# DDR3LChip.net
KiCad netlist of a schematic drawn in Altium Designer
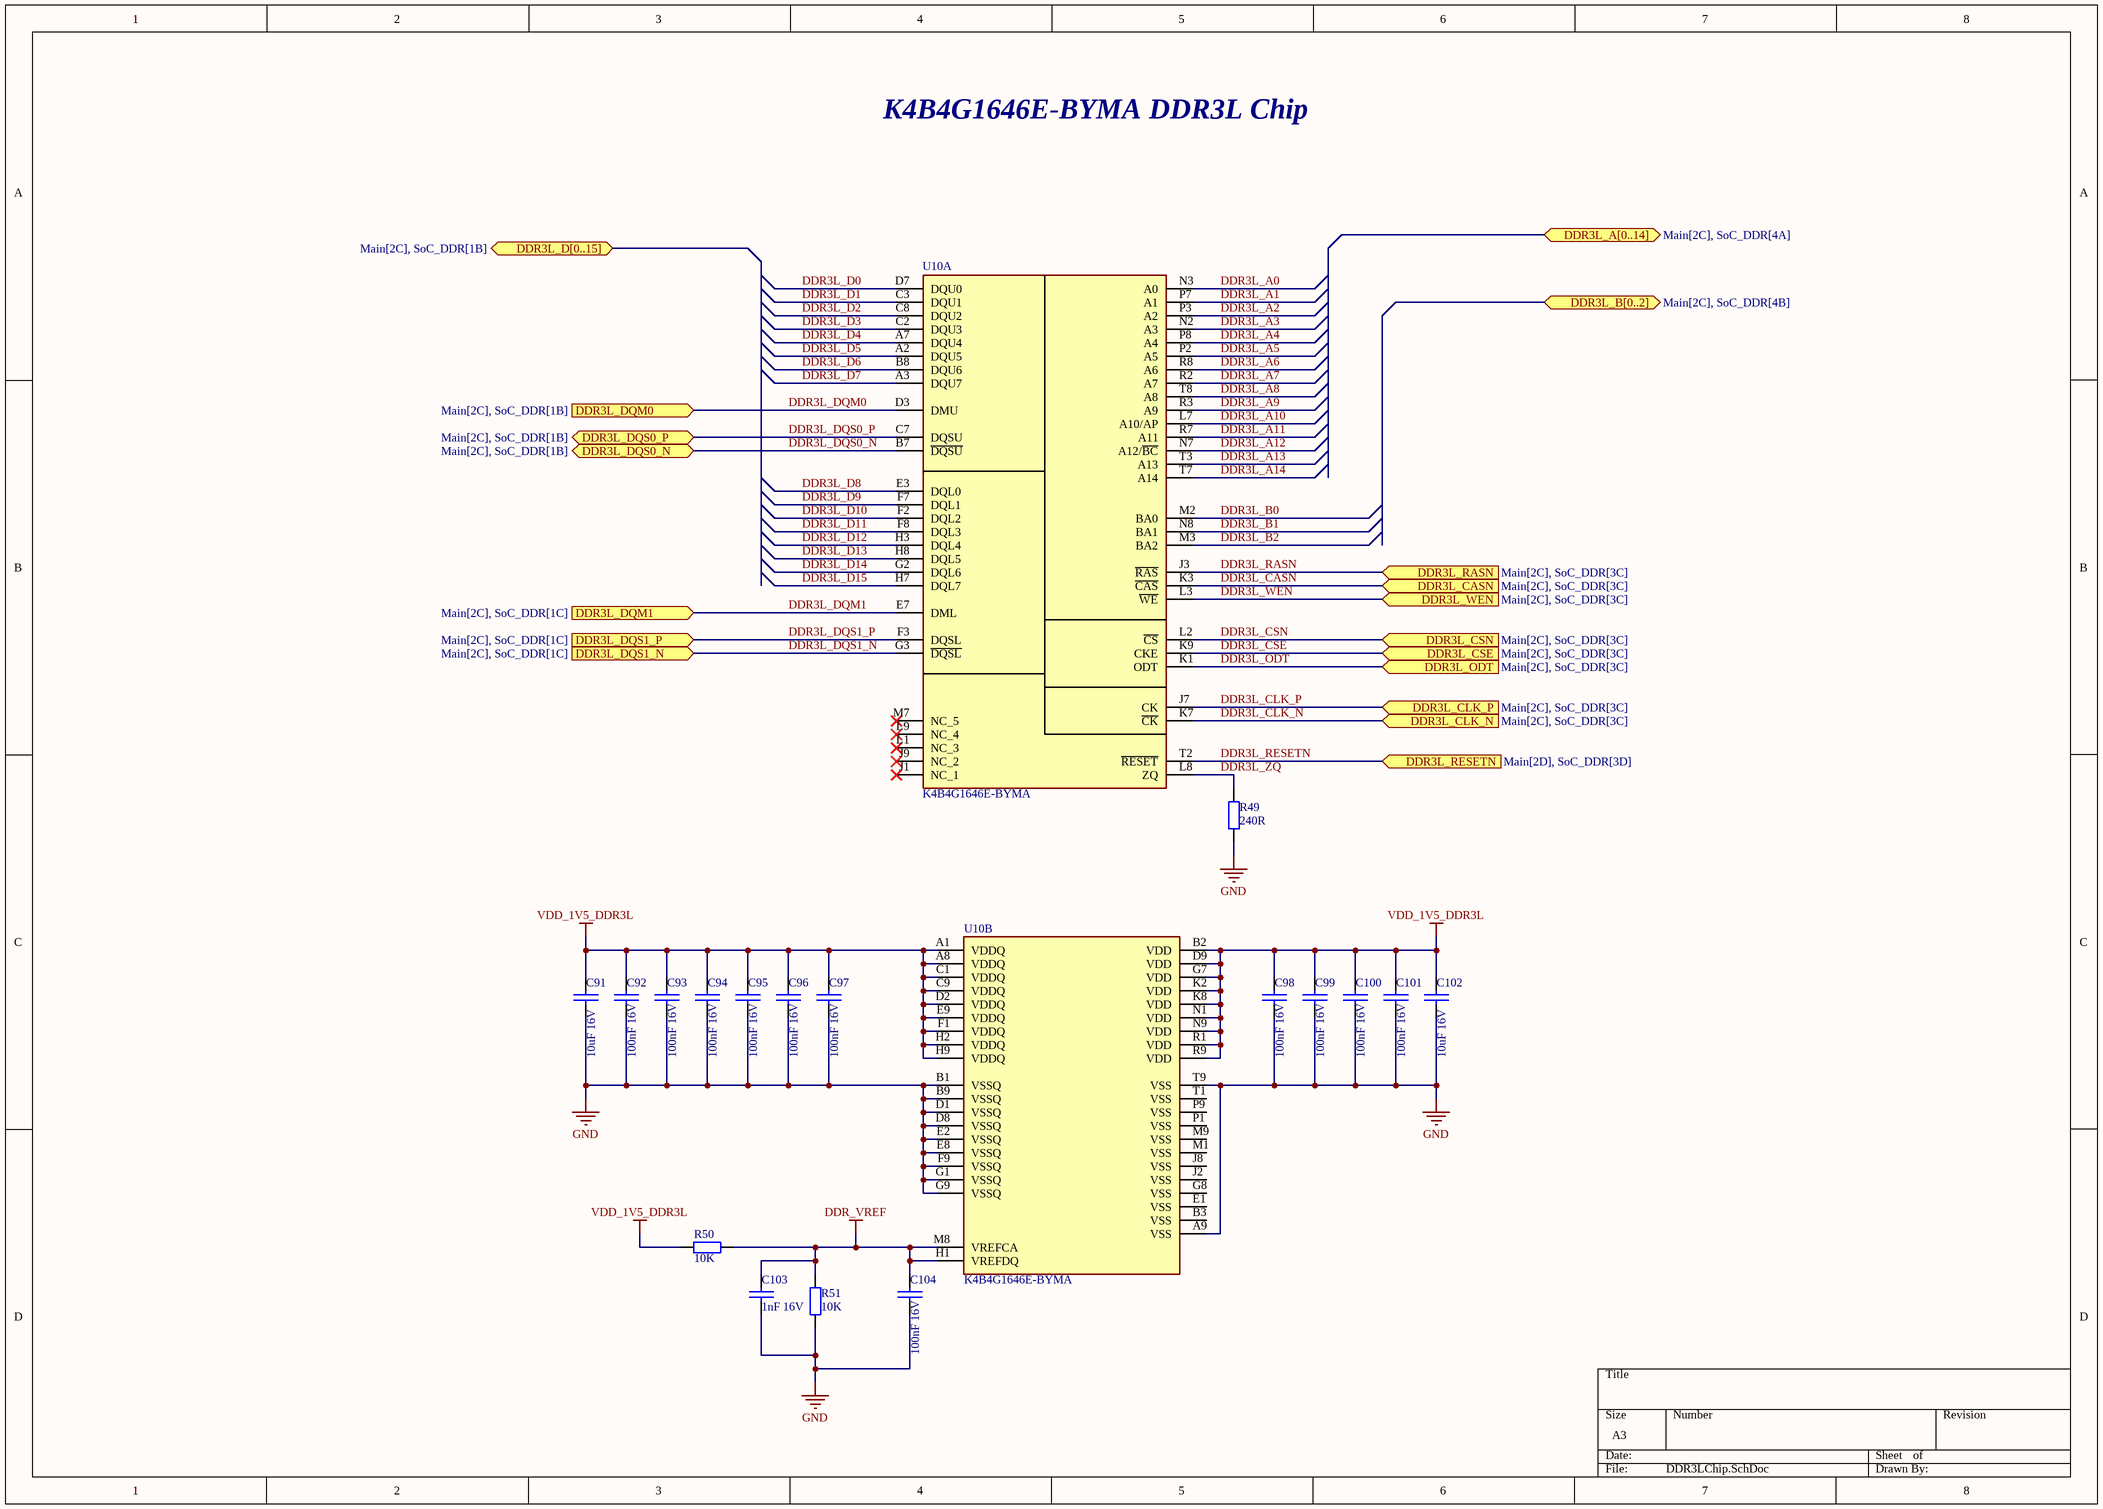
[diagram p0: DDR3LChip.SchDoc]

(export (version "E")
  (design (tool "Eeschema 10.0.6"))
  (components
    (comp (ref "C91")
      (value "10uF 16V")
      (footprint "C_0603")
      (description "Capacitor 0603 SMD")
      (libsource (lib "tor1kkLib") (part "C_0603"))
    )
    (comp (ref "C92")
      (value "100nF 16V")
      (footprint "C_0402")
      (description "Capacitor 0402 SMD")
      (libsource (lib "tor1kkLib") (part "C_0402"))
    )
    (comp (ref "C93")
      (value "100nF 16V")
      (footprint "C_0402")
      (description "Capacitor 0402 SMD")
      (libsource (lib "tor1kkLib") (part "C_0402"))
    )
    (comp (ref "C94")
      (value "100nF 16V")
      (footprint "C_0402")
      (description "Capacitor 0402 SMD")
      (libsource (lib "tor1kkLib") (part "C_0402"))
    )
    (comp (ref "C95")
      (value "100nF 16V")
      (footprint "C_0402")
      (description "Capacitor 0402 SMD")
      (libsource (lib "tor1kkLib") (part "C_0402"))
    )
    (comp (ref "C96")
      (value "100nF 16V")
      (footprint "C_0402")
      (description "Capacitor 0402 SMD")
      (libsource (lib "tor1kkLib") (part "C_0402"))
    )
    (comp (ref "C97")
      (value "100nF 16V")
      (footprint "C_0402")
      (description "Capacitor 0402 SMD")
      (libsource (lib "tor1kkLib") (part "C_0402"))
    )
    (comp (ref "C98")
      (value "100nF 16V")
      (footprint "C_0402")
      (description "Capacitor 0402 SMD")
      (libsource (lib "tor1kkLib") (part "C_0402"))
    )
    (comp (ref "C99")
      (value "100nF 16V")
      (footprint "C_0402")
      (description "Capacitor 0402 SMD")
      (libsource (lib "tor1kkLib") (part "C_0402"))
    )
    (comp (ref "C100")
      (value "100nF 16V")
      (footprint "C_0402")
      (description "Capacitor 0402 SMD")
      (libsource (lib "tor1kkLib") (part "C_0402"))
    )
    (comp (ref "C101")
      (value "100nF 16V")
      (footprint "C_0402")
      (description "Capacitor 0402 SMD")
      (libsource (lib "tor1kkLib") (part "C_0402"))
    )
    (comp (ref "C102")
      (value "10uF 16V")
      (footprint "C_0603")
      (description "Capacitor 0603 SMD")
      (libsource (lib "tor1kkLib") (part "C_0603"))
    )
    (comp (ref "C103")
      (value "1nF 16V")
      (footprint "C_0402")
      (description "Capacitor 0402 SMD")
      (libsource (lib "tor1kkLib") (part "C_0402"))
    )
    (comp (ref "C104")
      (value "100nF 16V")
      (footprint "C_0402")
      (description "Capacitor 0402 SMD")
      (libsource (lib "tor1kkLib") (part "C_0402"))
    )
    (comp (ref "R49")
      (value "240R")
      (footprint "R_0402")
      (description "Resistor 0402 SMD")
      (libsource (lib "") (part "R_0402_2"))
    )
    (comp (ref "R50")
      (value "10K")
      (footprint "R_0402")
      (description "Resistor 0402 SMD")
      (libsource (lib "") (part "R_0402_1"))
    )
    (comp (ref "R51")
      (value "10K")
      (footprint "R_0402")
      (description "Resistor 0402 SMD")
      (libsource (lib "tor1kkLib") (part "R_0402"))
    )
    (comp (ref "U10")
      (value "K4B4G1646E-BYMA")
      (footprint "BGA96C80P9X16_750X1330X120")
      (description "4Gbit SDRAM DDR3L 933MHz FBGA-96(7.5x13.3) DDR SDRAM ROHS")
      (libsource (lib "tor1kkLib") (part "K4B4G1646E-BYMA"))
    )
  )
  (nets
    (net (code "1") (name "/DDR3L_A0") (class "Default")
      (node (ref "U10") (pin "N3") (pinfunction "A0_N3") (pintype "passive"))
    )
    (net (code "2") (name "/DDR3L_A1") (class "Default")
      (node (ref "U10") (pin "P7") (pinfunction "A1_P7") (pintype "passive"))
    )
    (net (code "3") (name "/DDR3L_A2") (class "Default")
      (node (ref "U10") (pin "P3") (pinfunction "A2_P3") (pintype "passive"))
    )
    (net (code "4") (name "/DDR3L_A3") (class "Default")
      (node (ref "U10") (pin "N2") (pinfunction "A3_N2") (pintype "passive"))
    )
    (net (code "5") (name "/DDR3L_A4") (class "Default")
      (node (ref "U10") (pin "P8") (pinfunction "A4_P8") (pintype "passive"))
    )
    (net (code "6") (name "/DDR3L_A5") (class "Default")
      (node (ref "U10") (pin "P2") (pinfunction "A5_P2") (pintype "passive"))
    )
    (net (code "7") (name "/DDR3L_A6") (class "Default")
      (node (ref "U10") (pin "R8") (pinfunction "A6_R8") (pintype "passive"))
    )
    (net (code "8") (name "/DDR3L_A7") (class "Default")
      (node (ref "U10") (pin "R2") (pinfunction "A7_R2") (pintype "passive"))
    )
    (net (code "9") (name "/DDR3L_A8") (class "Default")
      (node (ref "U10") (pin "T8") (pinfunction "A8_T8") (pintype "passive"))
    )
    (net (code "10") (name "/DDR3L_A9") (class "Default")
      (node (ref "U10") (pin "R3") (pinfunction "A9_R3") (pintype "passive"))
    )
    (net (code "11") (name "/DDR3L_A10") (class "Default")
      (node (ref "U10") (pin "L7") (pinfunction "A10/AP_L7") (pintype "passive"))
    )
    (net (code "12") (name "/DDR3L_A11") (class "Default")
      (node (ref "U10") (pin "R7") (pinfunction "A11_R7") (pintype "passive"))
    )
    (net (code "13") (name "/DDR3L_A12") (class "Default")
      (node (ref "U10") (pin "N7") (pinfunction "A12/~{BC}_N7") (pintype "passive"))
    )
    (net (code "14") (name "/DDR3L_A13") (class "Default")
      (node (ref "U10") (pin "T3") (pinfunction "A13_T3") (pintype "passive"))
    )
    (net (code "15") (name "/DDR3L_A14") (class "Default")
      (node (ref "U10") (pin "T7") (pinfunction "A14_T7") (pintype "passive"))
    )
    (net (code "17") (name "/DDR3L_B0") (class "Default")
      (node (ref "U10") (pin "M2") (pinfunction "BA0_M2") (pintype "passive"))
    )
    (net (code "18") (name "/DDR3L_B1") (class "Default")
      (node (ref "U10") (pin "N8") (pinfunction "BA1_N8") (pintype "passive"))
    )
    (net (code "19") (name "/DDR3L_B2") (class "Default")
      (node (ref "U10") (pin "M3") (pinfunction "BA2_M3") (pintype "passive"))
    )
    (net (code "21") (name "/DDR3L_CASN") (class "Default")
      (node (ref "U10") (pin "K3") (pinfunction "~{CAS}_K3") (pintype "passive"))
    )
    (net (code "22") (name "/DDR3L_CLK_N") (class "Default")
      (node (ref "U10") (pin "K7") (pinfunction "~{CK}_K7") (pintype "passive"))
    )
    (net (code "23") (name "/DDR3L_CLK_P") (class "Default")
      (node (ref "U10") (pin "J7") (pinfunction "CK_J7") (pintype "passive"))
    )
    (net (code "24") (name "/DDR3L_CSE") (class "Default")
      (node (ref "U10") (pin "K9") (pinfunction "CKE_K9") (pintype "passive"))
    )
    (net (code "25") (name "/DDR3L_CSN") (class "Default")
      (node (ref "U10") (pin "L2") (pinfunction "~{CS}_L2") (pintype "passive"))
    )
    (net (code "26") (name "/DDR3L_D0") (class "Default")
      (node (ref "U10") (pin "D7") (pinfunction "DQU0_D7") (pintype "passive"))
    )
    (net (code "27") (name "/DDR3L_D1") (class "Default")
      (node (ref "U10") (pin "C3") (pinfunction "DQU1_C3") (pintype "passive"))
    )
    (net (code "28") (name "/DDR3L_D2") (class "Default")
      (node (ref "U10") (pin "C8") (pinfunction "DQU2_C8") (pintype "passive"))
    )
    (net (code "29") (name "/DDR3L_D3") (class "Default")
      (node (ref "U10") (pin "C2") (pinfunction "DQU3_C2") (pintype "passive"))
    )
    (net (code "30") (name "/DDR3L_D4") (class "Default")
      (node (ref "U10") (pin "A7") (pinfunction "DQU4_A7") (pintype "passive"))
    )
    (net (code "31") (name "/DDR3L_D5") (class "Default")
      (node (ref "U10") (pin "A2") (pinfunction "DQU5_A2") (pintype "passive"))
    )
    (net (code "32") (name "/DDR3L_D6") (class "Default")
      (node (ref "U10") (pin "B8") (pinfunction "DQU6_B8") (pintype "passive"))
    )
    (net (code "33") (name "/DDR3L_D7") (class "Default")
      (node (ref "U10") (pin "A3") (pinfunction "DQU7_A3") (pintype "passive"))
    )
    (net (code "34") (name "/DDR3L_D8") (class "Default")
      (node (ref "U10") (pin "E3") (pinfunction "DQL0_E3") (pintype "passive"))
    )
    (net (code "35") (name "/DDR3L_D9") (class "Default")
      (node (ref "U10") (pin "F7") (pinfunction "DQL1_F7") (pintype "passive"))
    )
    (net (code "36") (name "/DDR3L_D10") (class "Default")
      (node (ref "U10") (pin "F2") (pinfunction "DQL2_F2") (pintype "passive"))
    )
    (net (code "37") (name "/DDR3L_D11") (class "Default")
      (node (ref "U10") (pin "F8") (pinfunction "DQL3_F8") (pintype "passive"))
    )
    (net (code "38") (name "/DDR3L_D12") (class "Default")
      (node (ref "U10") (pin "H3") (pinfunction "DQL4_H3") (pintype "passive"))
    )
    (net (code "39") (name "/DDR3L_D13") (class "Default")
      (node (ref "U10") (pin "H8") (pinfunction "DQL5_H8") (pintype "passive"))
    )
    (net (code "40") (name "/DDR3L_D14") (class "Default")
      (node (ref "U10") (pin "G2") (pinfunction "DQL6_G2") (pintype "passive"))
    )
    (net (code "41") (name "/DDR3L_D15") (class "Default")
      (node (ref "U10") (pin "H7") (pinfunction "DQL7_H7") (pintype "passive"))
    )
    (net (code "42") (name "/DDR3L_DQM0") (class "Default")
      (node (ref "U10") (pin "D3") (pinfunction "DMU_D3") (pintype "passive"))
    )
    (net (code "43") (name "/DDR3L_DQM1") (class "Default")
      (node (ref "U10") (pin "E7") (pinfunction "DML_E7") (pintype "passive"))
    )
    (net (code "44") (name "/DDR3L_DQS0_N") (class "Default")
      (node (ref "U10") (pin "B7") (pinfunction "~{DQSU}_B7") (pintype "passive"))
    )
    (net (code "45") (name "/DDR3L_DQS0_P") (class "Default")
      (node (ref "U10") (pin "C7") (pinfunction "DQSU_C7") (pintype "passive"))
    )
    (net (code "46") (name "/DDR3L_DQS1_N") (class "Default")
      (node (ref "U10") (pin "G3") (pinfunction "~{DQSL}_G3") (pintype "passive"))
    )
    (net (code "47") (name "/DDR3L_DQS1_P") (class "Default")
      (node (ref "U10") (pin "F3") (pinfunction "DQSL_F3") (pintype "passive"))
    )
    (net (code "49") (name "/DDR3L_ODT") (class "Default")
      (node (ref "U10") (pin "K1") (pinfunction "ODT_K1") (pintype "passive"))
    )
    (net (code "50") (name "/DDR3L_RASN") (class "Default")
      (node (ref "U10") (pin "J3") (pinfunction "~{RAS}_J3") (pintype "passive"))
    )
    (net (code "51") (name "/DDR3L_RESETN") (class "Default")
      (node (ref "U10") (pin "T2") (pinfunction "~{RESET}_T2") (pintype "passive"))
    )
    (net (code "52") (name "/DDR3L_WEN") (class "Default")
      (node (ref "U10") (pin "L3") (pinfunction "~{WE}_L3") (pintype "passive"))
    )
    (net (code "53") (name "/DDR3L_ZQ") (class "Default")
      (node (ref "R49") (pin "2") (pintype "passive"))
      (node (ref "U10") (pin "L8") (pinfunction "ZQ_L8") (pintype "passive"))
    )
    (net (code "54") (name "DDR_VREF") (class "Default")
      (node (ref "C103") (pin "1") (pintype "passive"))
      (node (ref "C104") (pin "1") (pintype "passive"))
      (node (ref "R50") (pin "1") (pintype "passive"))
      (node (ref "R51") (pin "1") (pintype "passive"))
      (node (ref "U10") (pin "H1") (pinfunction "VREFDQ_H1") (pintype "passive"))
      (node (ref "U10") (pin "M8") (pinfunction "VREFCA_M8") (pintype "passive"))
    )
    (net (code "55") (name "GND") (class "Default")
      (node (ref "C100") (pin "2") (pintype "passive"))
      (node (ref "C101") (pin "2") (pintype "passive"))
      (node (ref "C102") (pin "2") (pintype "passive"))
      (node (ref "C103") (pin "2") (pintype "passive"))
      (node (ref "C104") (pin "2") (pintype "passive"))
      (node (ref "C91") (pin "2") (pintype "passive"))
      (node (ref "C92") (pin "2") (pintype "passive"))
      (node (ref "C93") (pin "2") (pintype "passive"))
      (node (ref "C94") (pin "2") (pintype "passive"))
      (node (ref "C95") (pin "2") (pintype "passive"))
      (node (ref "C96") (pin "2") (pintype "passive"))
      (node (ref "C97") (pin "2") (pintype "passive"))
      (node (ref "C98") (pin "2") (pintype "passive"))
      (node (ref "C99") (pin "2") (pintype "passive"))
      (node (ref "R49") (pin "1") (pintype "passive"))
      (node (ref "R51") (pin "2") (pintype "passive"))
      (node (ref "U10") (pin "A9") (pinfunction "VSS_A9") (pintype "passive"))
      (node (ref "U10") (pin "B1") (pinfunction "VSSQ_B1") (pintype "passive"))
      (node (ref "U10") (pin "B9") (pinfunction "VSSQ_B9") (pintype "passive"))
      (node (ref "U10") (pin "D1") (pinfunction "VSSQ_D1") (pintype "passive"))
      (node (ref "U10") (pin "D8") (pinfunction "VSSQ_D8") (pintype "passive"))
      (node (ref "U10") (pin "E2") (pinfunction "VSSQ_E2") (pintype "passive"))
      (node (ref "U10") (pin "E8") (pinfunction "VSSQ_E8") (pintype "passive"))
      (node (ref "U10") (pin "F9") (pinfunction "VSSQ_F9") (pintype "passive"))
      (node (ref "U10") (pin "G1") (pinfunction "VSSQ_G1") (pintype "passive"))
      (node (ref "U10") (pin "G9") (pinfunction "VSSQ_G9") (pintype "passive"))
      (node (ref "U10") (pin "T9") (pinfunction "VSS_T9") (pintype "passive"))
    )
    (net (code "56") (name "VDD_1V5_DDR3L") (class "Default")
      (node (ref "C100") (pin "1") (pintype "passive"))
      (node (ref "C101") (pin "1") (pintype "passive"))
      (node (ref "C102") (pin "1") (pintype "passive"))
      (node (ref "C91") (pin "1") (pintype "passive"))
      (node (ref "C92") (pin "1") (pintype "passive"))
      (node (ref "C93") (pin "1") (pintype "passive"))
      (node (ref "C94") (pin "1") (pintype "passive"))
      (node (ref "C95") (pin "1") (pintype "passive"))
      (node (ref "C96") (pin "1") (pintype "passive"))
      (node (ref "C97") (pin "1") (pintype "passive"))
      (node (ref "C98") (pin "1") (pintype "passive"))
      (node (ref "C99") (pin "1") (pintype "passive"))
      (node (ref "R50") (pin "2") (pintype "passive"))
      (node (ref "U10") (pin "A1") (pinfunction "VDDQ_A1") (pintype "passive"))
      (node (ref "U10") (pin "A8") (pinfunction "VDDQ_A8") (pintype "passive"))
      (node (ref "U10") (pin "B2") (pinfunction "VDD_B2") (pintype "passive"))
      (node (ref "U10") (pin "C1") (pinfunction "VDDQ_C1") (pintype "passive"))
      (node (ref "U10") (pin "C9") (pinfunction "VDDQ_C9") (pintype "passive"))
      (node (ref "U10") (pin "D2") (pinfunction "VDDQ_D2") (pintype "passive"))
      (node (ref "U10") (pin "D9") (pinfunction "VDD_D9") (pintype "passive"))
      (node (ref "U10") (pin "E9") (pinfunction "VDDQ_E9") (pintype "passive"))
      (node (ref "U10") (pin "F1") (pinfunction "VDDQ_F1") (pintype "passive"))
      (node (ref "U10") (pin "G7") (pinfunction "VDD_G7") (pintype "passive"))
      (node (ref "U10") (pin "H2") (pinfunction "VDDQ_H2") (pintype "passive"))
      (node (ref "U10") (pin "H9") (pinfunction "VDDQ_H9") (pintype "passive"))
      (node (ref "U10") (pin "K2") (pinfunction "VDD_K2") (pintype "passive"))
      (node (ref "U10") (pin "K8") (pinfunction "VDD_K8") (pintype "passive"))
      (node (ref "U10") (pin "N1") (pinfunction "VDD_N1") (pintype "passive"))
      (node (ref "U10") (pin "N9") (pinfunction "VDD_N9") (pintype "passive"))
      (node (ref "U10") (pin "R1") (pinfunction "VDD_R1") (pintype "passive"))
      (node (ref "U10") (pin "R9") (pinfunction "VDD_R9") (pintype "passive"))
    )
    (net (code "57") (name "unconnected-(U10A-NC_1-PadJ1)") (class "Default")
      (node (ref "U10") (pin "J1") (pinfunction "NC_1_J1") (pintype "passive+no_connect"))
    )
    (net (code "58") (name "unconnected-(U10A-NC_2-PadJ9)") (class "Default")
      (node (ref "U10") (pin "J9") (pinfunction "NC_2_J9") (pintype "passive+no_connect"))
    )
    (net (code "59") (name "unconnected-(U10A-NC_3-PadL1)") (class "Default")
      (node (ref "U10") (pin "L1") (pinfunction "NC_3_L1") (pintype "passive+no_connect"))
    )
    (net (code "60") (name "unconnected-(U10A-NC_4-PadL9)") (class "Default")
      (node (ref "U10") (pin "L9") (pinfunction "NC_4_L9") (pintype "passive+no_connect"))
    )
    (net (code "61") (name "unconnected-(U10A-NC_5-PadM7)") (class "Default")
      (node (ref "U10") (pin "M7") (pinfunction "NC_5_M7") (pintype "passive+no_connect"))
    )
    (net (code "62") (name "unconnected-(U10B-VSS-PadB3)") (class "Default")
      (node (ref "U10") (pin "B3") (pinfunction "VSS_B3") (pintype "passive"))
    )
    (net (code "63") (name "unconnected-(U10B-VSS-PadE1)") (class "Default")
      (node (ref "U10") (pin "E1") (pinfunction "VSS_E1") (pintype "passive"))
    )
    (net (code "64") (name "unconnected-(U10B-VSS-PadG8)") (class "Default")
      (node (ref "U10") (pin "G8") (pinfunction "VSS_G8") (pintype "passive"))
    )
    (net (code "65") (name "unconnected-(U10B-VSS-PadJ2)") (class "Default")
      (node (ref "U10") (pin "J2") (pinfunction "VSS_J2") (pintype "passive"))
    )
    (net (code "66") (name "unconnected-(U10B-VSS-PadJ8)") (class "Default")
      (node (ref "U10") (pin "J8") (pinfunction "VSS_J8") (pintype "passive"))
    )
    (net (code "67") (name "unconnected-(U10B-VSS-PadM1)") (class "Default")
      (node (ref "U10") (pin "M1") (pinfunction "VSS_M1") (pintype "passive"))
    )
    (net (code "68") (name "unconnected-(U10B-VSS-PadM9)") (class "Default")
      (node (ref "U10") (pin "M9") (pinfunction "VSS_M9") (pintype "passive"))
    )
    (net (code "69") (name "unconnected-(U10B-VSS-PadP1)") (class "Default")
      (node (ref "U10") (pin "P1") (pinfunction "VSS_P1") (pintype "passive"))
    )
    (net (code "70") (name "unconnected-(U10B-VSS-PadP9)") (class "Default")
      (node (ref "U10") (pin "P9") (pinfunction "VSS_P9") (pintype "passive"))
    )
    (net (code "71") (name "unconnected-(U10B-VSS-PadT1)") (class "Default")
      (node (ref "U10") (pin "T1") (pinfunction "VSS_T1") (pintype "passive"))
    )
  )
)
